# HDMI_OUT.net
KiCad netlist of a schematic drawn in Altium Designer
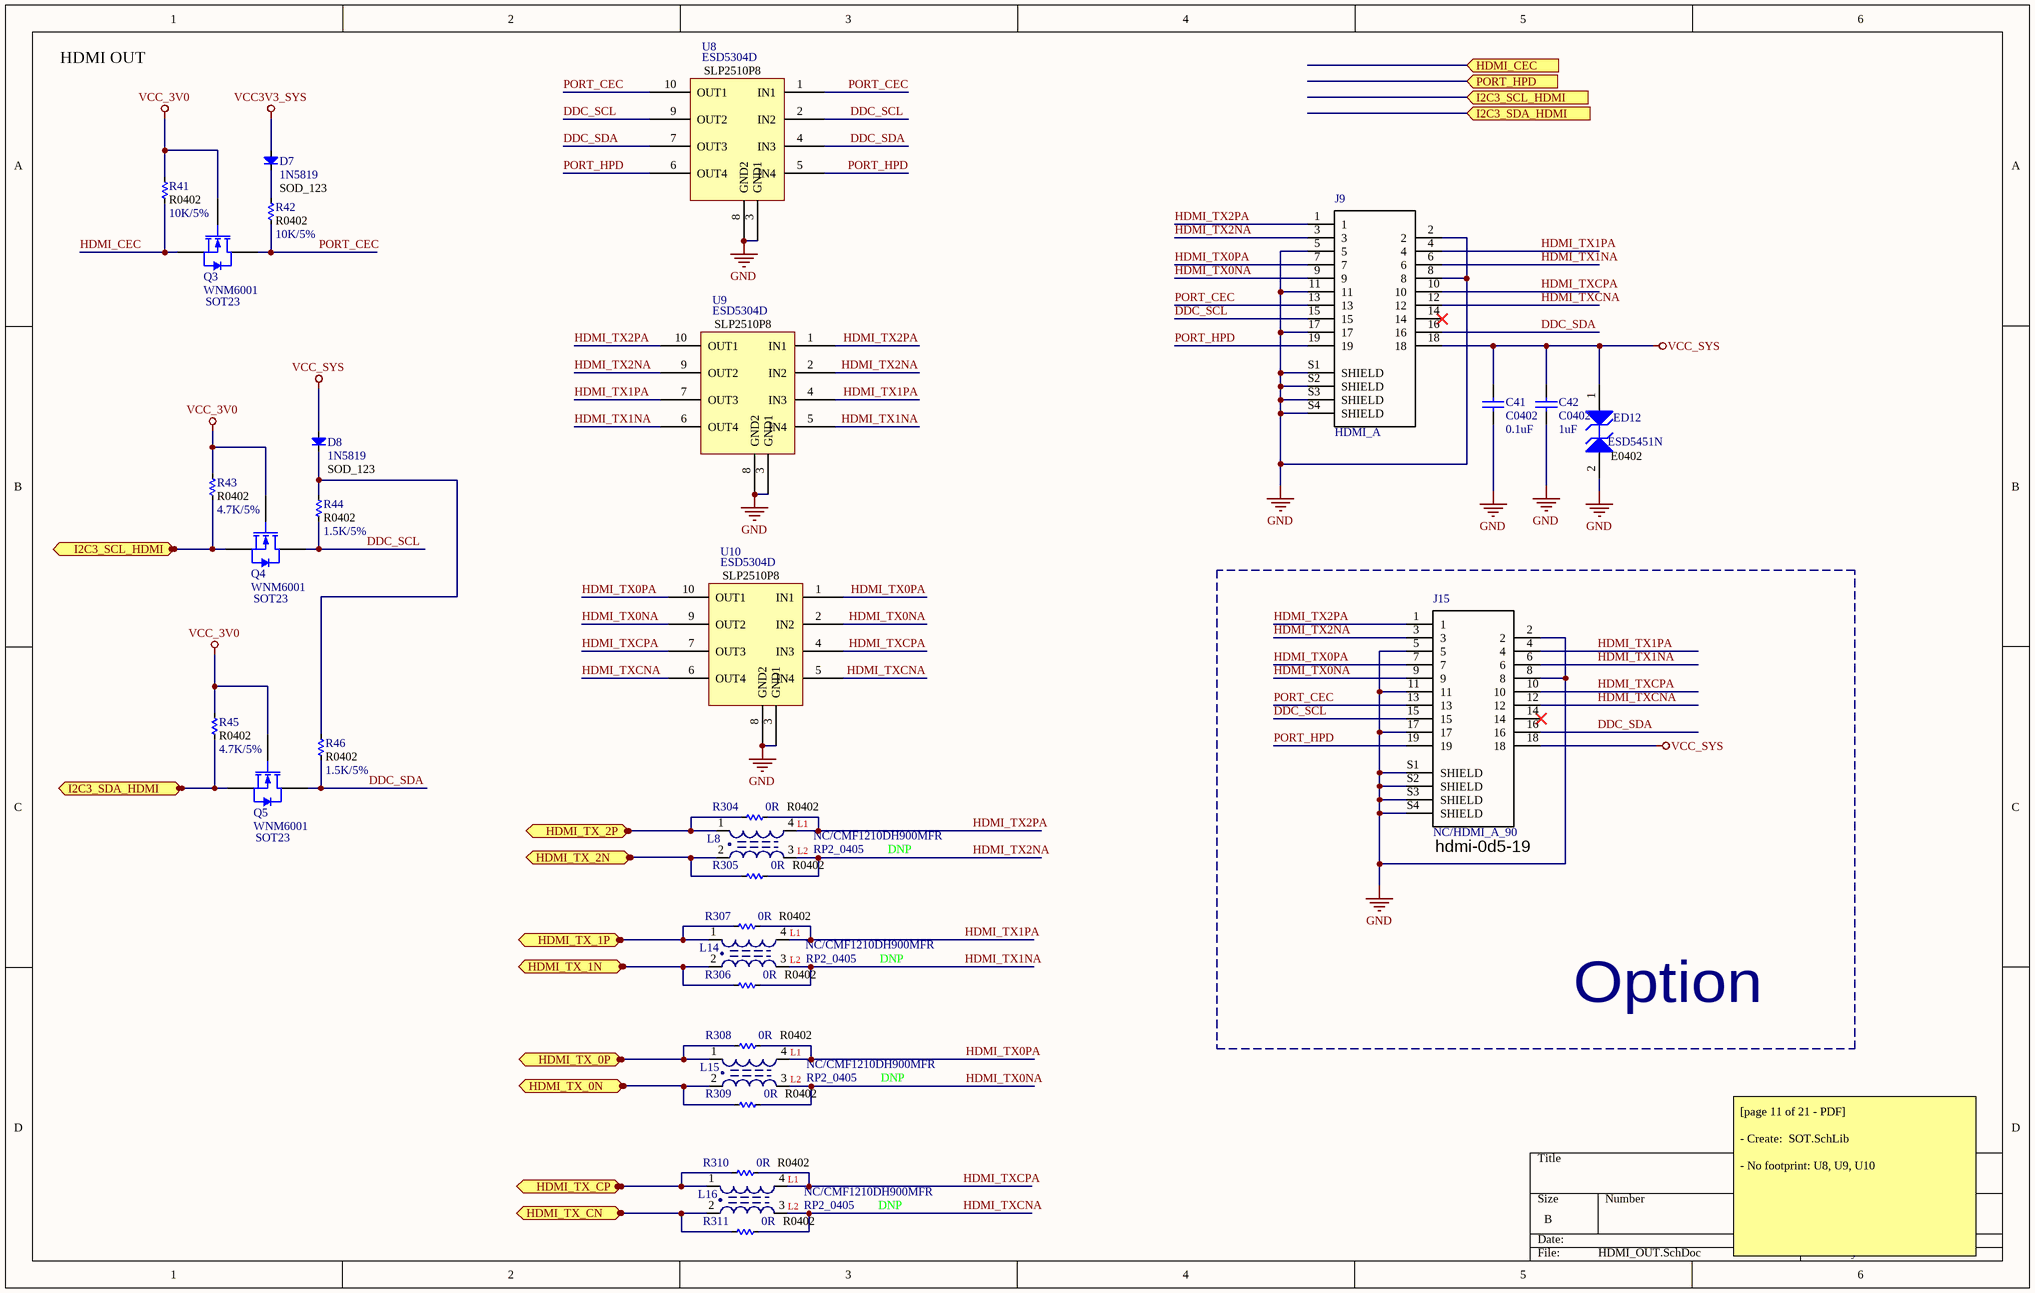
[diagram p0: HDMI_OUT.SchDoc]

(export (version "E")
  (design (tool "Eeschema 10.0.6"))
  (components
    (comp (ref "C41")
      (value "C0402")
      (footprint "C 0402")
      (description "Capacitor")
      (fields (field (name "ALTIUM_VALUE") "0.1uF") (field (name "PUBLISHER") "Altium Limited"))
      (libsource (lib "Miscellaneous Devices") (part "Cap"))
    )
    (comp (ref "C42")
      (value "C0402")
      (footprint "C 0402")
      (description "Capacitor")
      (fields (field (name "ALTIUM_VALUE") "1uF") (field (name "PUBLISHER") "Altium Limited"))
      (libsource (lib "Miscellaneous Devices") (part "Cap"))
    )
    (comp (ref "D7")
      (value "1N5819")
      (footprint "DIO-SMD-123")
      (description "Default Diode")
      (fields
        (field (name "TYPR") "SOD_123")
        (field (name "Comment") "Diode SMD")
        (field (name "PUBLISHER") "Altium Limited")
      )
      (libsource (lib "LIBRARY") (part "Diode SMD"))
    )
    (comp (ref "D8")
      (value "1N5819")
      (footprint "DIO-SMD-123")
      (description "Default Diode")
      (fields
        (field (name "TYPR") "SOD_123")
        (field (name "Comment") "Diode SMD")
        (field (name "PUBLISHER") "Altium Limited")
      )
      (libsource (lib "LIBRARY") (part "Diode SMD"))
    )
    (comp (ref "ED12")
      (value "ESD5451N")
      (footprint "DFN1006-2L")
      (description "600 W Peak Power Zener Transient Voltage Suppressor, Bidirectional, 2-Pin SMB, Tape and Reel")
      (fields
        (field (name "MANUFACTURER") "On Semiconductor")
        (field (name "PARTNUMBER") "1SMB54CAT3")
        (field (name "ALTIUM_UNNAMED_1") "E0402")
      )
      (libsource (lib "ON Semi Transient Voltage Suppressors (TVS)") (part "1SMB54CAT3"))
    )
    (comp (ref "J9")
      (value "HDMI_A")
      (footprint "*AMPHENOL_10029449-001RLF_10029449-001RLF(Primary)")
      (description "Connector, Hdmi Type a, Receptacle, 19 Position, Full Reel")
      (fields (field (name "MP") "10029449-001RLF") (field (name "MF") "Amphenol ICC"))
      (libsource (lib "10029449-001RLF") (part "10029449-001RLF"))
    )
    (comp (ref "J15")
      (value "NC/HDMI_A_90")
      (footprint "*AMPHENOL_10029449-001RLF_10029449-001RLF(Primary)")
      (description "Connector, Hdmi Type a, Receptacle, 19 Position, Full Reel")
      (fields
        (field (name "MP") "10029449-001RLF")
        (field (name "PACKAGE") "hdmi-0d5-19")
        (field (name "MF") "Amphenol ICC")
      )
      (libsource (lib "10029449-001RLF") (part "10029449-001RLF"))
    )
    (comp (ref "L8")
      (value "RP2_0405")
      (footprint "L-SMD-D-7.3x7.3")
      (fields
        (field (name "PARTNO") "7448709022")
        (field (name "MANUFACTURER") "Würth Elektronik eiSos GmbH")
        (field (name "ALTIUM_UNNAMED_1") "NC/CMF1210DH900MFR")
        (field (name "ALTIUM_UNNAMED_2") "DNP")
        (field (name "CREATED BY") "Christin Otto")
      )
      (libsource (lib "LIBRARY") (part "L-SMD-2"))
    )
    (comp (ref "L14")
      (value "RP2_0405")
      (footprint "L-SMD-D-7.3x7.3")
      (fields
        (field (name "PARTNO") "7448709022")
        (field (name "MANUFACTURER") "Würth Elektronik eiSos GmbH")
        (field (name "ALTIUM_UNNAMED_1") "NC/CMF1210DH900MFR")
        (field (name "ALTIUM_UNNAMED_2") "DNP")
        (field (name "CREATED BY") "Christin Otto")
      )
      (libsource (lib "LIBRARY") (part "L-SMD-2"))
    )
    (comp (ref "L15")
      (value "RP2_0405")
      (footprint "L-SMD-D-7.3x7.3")
      (fields
        (field (name "PARTNO") "7448709022")
        (field (name "MANUFACTURER") "Würth Elektronik eiSos GmbH")
        (field (name "ALTIUM_UNNAMED_1") "NC/CMF1210DH900MFR")
        (field (name "ALTIUM_UNNAMED_2") "DNP")
        (field (name "CREATED BY") "Christin Otto")
      )
      (libsource (lib "LIBRARY") (part "L-SMD-2"))
    )
    (comp (ref "L16")
      (value "RP2_0405")
      (footprint "L-SMD-D-7.3x7.3")
      (fields
        (field (name "PARTNO") "7448709022")
        (field (name "MANUFACTURER") "Würth Elektronik eiSos GmbH")
        (field (name "ALTIUM_UNNAMED_1") "NC/CMF1210DH900MFR")
        (field (name "ALTIUM_UNNAMED_2") "DNP")
        (field (name "CREATED BY") "Christin Otto")
      )
      (libsource (lib "LIBRARY") (part "L-SMD-2"))
    )
    (comp (ref "Q3")
      (value "WNM6001")
      (footprint "SOT23")
      (description "20V N-Channel Enhancement Mode MOSFET")
      (fields (field (name "PACKAGEREFERENCE") "SOT23") (field (name "PUBLISHER") "Altium Limited"))
      (libsource (lib "Zetex Discrete MOSFET") (part "ZXM61N02F"))
    )
    (comp (ref "Q4")
      (value "WNM6001")
      (footprint "SOT23")
      (description "20V N-Channel Enhancement Mode MOSFET")
      (fields (field (name "PACKAGEREFERENCE") "SOT23") (field (name "PUBLISHER") "Altium Limited"))
      (libsource (lib "Zetex Discrete MOSFET") (part "ZXM61N02F"))
    )
    (comp (ref "Q5")
      (value "WNM6001")
      (footprint "SOT23")
      (description "20V N-Channel Enhancement Mode MOSFET")
      (fields (field (name "PACKAGEREFERENCE") "SOT23") (field (name "PUBLISHER") "Altium Limited"))
      (libsource (lib "Zetex Discrete MOSFET") (part "ZXM61N02F"))
    )
    (comp (ref "R41")
      (value "R0402")
      (footprint "R 0402")
      (description "Resistor")
      (fields
        (field (name "MANUFACTURER") "Generic Components")
        (field (name "ALTIUM_VALUE") "10K/5%")
        (field (name "PUBLISHER") "Altium Hobart Technology Centre")
      )
      (libsource (lib "LIBRARY") (part "Res-SMD"))
    )
    (comp (ref "R42")
      (value "R0402")
      (footprint "R 0402")
      (description "Resistor")
      (fields
        (field (name "MANUFACTURER") "Generic Components")
        (field (name "ALTIUM_VALUE") "10K/5%")
        (field (name "PUBLISHER") "Altium Hobart Technology Centre")
      )
      (libsource (lib "LIBRARY") (part "Res-SMD"))
    )
    (comp (ref "R43")
      (value "R0402")
      (footprint "R 0402")
      (description "Resistor")
      (fields
        (field (name "MANUFACTURER") "Generic Components")
        (field (name "ALTIUM_VALUE") "4.7K/5%")
        (field (name "PUBLISHER") "Altium Hobart Technology Centre")
      )
      (libsource (lib "LIBRARY") (part "Res-SMD"))
    )
    (comp (ref "R44")
      (value "R0402")
      (footprint "R 0402")
      (description "Resistor")
      (fields
        (field (name "MANUFACTURER") "Generic Components")
        (field (name "ALTIUM_VALUE") "1.5K/5%")
        (field (name "PUBLISHER") "Altium Hobart Technology Centre")
      )
      (libsource (lib "LIBRARY") (part "Res-SMD"))
    )
    (comp (ref "R45")
      (value "R0402")
      (footprint "R 0402")
      (description "Resistor")
      (fields
        (field (name "MANUFACTURER") "Generic Components")
        (field (name "ALTIUM_VALUE") "4.7K/5%")
        (field (name "PUBLISHER") "Altium Hobart Technology Centre")
      )
      (libsource (lib "LIBRARY") (part "Res-SMD"))
    )
    (comp (ref "R46")
      (value "R0402")
      (footprint "R 0402")
      (description "Resistor")
      (fields
        (field (name "MANUFACTURER") "Generic Components")
        (field (name "ALTIUM_VALUE") "1.5K/5%")
        (field (name "PUBLISHER") "Altium Hobart Technology Centre")
      )
      (libsource (lib "LIBRARY") (part "Res-SMD"))
    )
    (comp (ref "R304")
      (value "R0402")
      (footprint "R 0402")
      (description "Resistor")
      (fields
        (field (name "MANUFACTURER") "Generic Components")
        (field (name "ALTIUM_VALUE") "0R")
        (field (name "PUBLISHER") "Altium Hobart Technology Centre")
      )
      (libsource (lib "LIBRARY") (part "Res-SMD"))
    )
    (comp (ref "R305")
      (value "R0402")
      (footprint "R 0402")
      (description "Resistor")
      (fields
        (field (name "MANUFACTURER") "Generic Components")
        (field (name "ALTIUM_VALUE") "0R")
        (field (name "PUBLISHER") "Altium Hobart Technology Centre")
      )
      (libsource (lib "LIBRARY") (part "Res-SMD"))
    )
    (comp (ref "R306")
      (value "R0402")
      (footprint "R 0402")
      (description "Resistor")
      (fields
        (field (name "MANUFACTURER") "Generic Components")
        (field (name "ALTIUM_VALUE") "0R")
        (field (name "PUBLISHER") "Altium Hobart Technology Centre")
      )
      (libsource (lib "LIBRARY") (part "Res-SMD"))
    )
    (comp (ref "R307")
      (value "R0402")
      (footprint "R 0402")
      (description "Resistor")
      (fields
        (field (name "MANUFACTURER") "Generic Components")
        (field (name "ALTIUM_VALUE") "0R")
        (field (name "PUBLISHER") "Altium Hobart Technology Centre")
      )
      (libsource (lib "LIBRARY") (part "Res-SMD"))
    )
    (comp (ref "R308")
      (value "R0402")
      (footprint "R 0402")
      (description "Resistor")
      (fields
        (field (name "MANUFACTURER") "Generic Components")
        (field (name "ALTIUM_VALUE") "0R")
        (field (name "PUBLISHER") "Altium Hobart Technology Centre")
      )
      (libsource (lib "LIBRARY") (part "Res-SMD"))
    )
    (comp (ref "R309")
      (value "R0402")
      (footprint "R 0402")
      (description "Resistor")
      (fields
        (field (name "MANUFACTURER") "Generic Components")
        (field (name "ALTIUM_VALUE") "0R")
        (field (name "PUBLISHER") "Altium Hobart Technology Centre")
      )
      (libsource (lib "LIBRARY") (part "Res-SMD"))
    )
    (comp (ref "R310")
      (value "R0402")
      (footprint "R 0402")
      (description "Resistor")
      (fields
        (field (name "MANUFACTURER") "Generic Components")
        (field (name "ALTIUM_VALUE") "0R")
        (field (name "PUBLISHER") "Altium Hobart Technology Centre")
      )
      (libsource (lib "LIBRARY") (part "Res-SMD"))
    )
    (comp (ref "R311")
      (value "R0402")
      (footprint "R 0402")
      (description "Resistor")
      (fields
        (field (name "MANUFACTURER") "Generic Components")
        (field (name "ALTIUM_VALUE") "0R")
        (field (name "PUBLISHER") "Altium Hobart Technology Centre")
      )
      (libsource (lib "LIBRARY") (part "Res-SMD"))
    )
    (comp (ref "U8")
      (value "ESD5304D")
      (footprint "RCLAMP0524PATCT")
      (libsource (lib "SOT") (part "SLP2510P8"))
    )
    (comp (ref "U9")
      (value "ESD5304D")
      (footprint "RCLAMP0524PATCT")
      (libsource (lib "SOT") (part "SLP2510P8"))
    )
    (comp (ref "U10")
      (value "ESD5304D")
      (footprint "RCLAMP0524PATCT")
      (libsource (lib "SOT") (part "SLP2510P8"))
    )
  )
  (nets
    (net (code "1") (name "/DDC_SCL") (class "Default")
      (node (ref "J15") (pin "15") (pinfunction "15_15") (pintype "passive"))
      (node (ref "J9") (pin "15") (pinfunction "15_15") (pintype "passive"))
      (node (ref "Q4") (pin "1") (pinfunction "D_1") (pintype "passive"))
      (node (ref "R44") (pin "1") (pinfunction "1_1") (pintype "passive"))
      (node (ref "U8") (pin "2") (pinfunction "IN2_2") (pintype "passive"))
      (node (ref "U8") (pin "9") (pinfunction "OUT2_9") (pintype "passive"))
    )
    (net (code "2") (name "/DDC_SDA") (class "Default")
      (node (ref "J15") (pin "16") (pinfunction "16_16") (pintype "passive"))
      (node (ref "J9") (pin "16") (pinfunction "16_16") (pintype "passive"))
      (node (ref "Q5") (pin "1") (pinfunction "D_1") (pintype "passive"))
      (node (ref "R46") (pin "1") (pinfunction "1_1") (pintype "passive"))
      (node (ref "U8") (pin "4") (pinfunction "IN3_4") (pintype "passive"))
      (node (ref "U8") (pin "7") (pinfunction "OUT3_7") (pintype "passive"))
    )
    (net (code "3") (name "/HDMI_CEC") (class "Default")
      (node (ref "Q3") (pin "2") (pinfunction "S_2") (pintype "passive"))
      (node (ref "R41") (pin "1") (pinfunction "1_1") (pintype "passive"))
    )
    (net (code "4") (name "/HDMI_TX0NA") (class "Default")
      (node (ref "J15") (pin "9") (pinfunction "9_9") (pintype "passive"))
      (node (ref "J9") (pin "9") (pinfunction "9_9") (pintype "passive"))
      (node (ref "L15") (pin "3") (pinfunction "3_3") (pintype "passive"))
      (node (ref "R309") (pin "1") (pinfunction "1_1") (pintype "passive"))
      (node (ref "U10") (pin "2") (pinfunction "IN2_2") (pintype "passive"))
      (node (ref "U10") (pin "9") (pinfunction "OUT2_9") (pintype "passive"))
    )
    (net (code "5") (name "/HDMI_TX0PA") (class "Default")
      (node (ref "J15") (pin "7") (pinfunction "7_7") (pintype "passive"))
      (node (ref "J9") (pin "7") (pinfunction "7_7") (pintype "passive"))
      (node (ref "L15") (pin "4") (pinfunction "4_4") (pintype "passive"))
      (node (ref "R308") (pin "1") (pinfunction "1_1") (pintype "passive"))
      (node (ref "U10") (pin "1") (pinfunction "IN1_1") (pintype "passive"))
      (node (ref "U10") (pin "10") (pinfunction "OUT1_10") (pintype "passive"))
    )
    (net (code "6") (name "/HDMI_TX1NA") (class "Default")
      (node (ref "J15") (pin "6") (pinfunction "6_6") (pintype "passive"))
      (node (ref "J9") (pin "6") (pinfunction "6_6") (pintype "passive"))
      (node (ref "L14") (pin "3") (pinfunction "3_3") (pintype "passive"))
      (node (ref "R306") (pin "1") (pinfunction "1_1") (pintype "passive"))
      (node (ref "U9") (pin "5") (pinfunction "IN4_5") (pintype "passive"))
      (node (ref "U9") (pin "6") (pinfunction "OUT4_6") (pintype "passive"))
    )
    (net (code "7") (name "/HDMI_TX1PA") (class "Default")
      (node (ref "J15") (pin "4") (pinfunction "4_4") (pintype "passive"))
      (node (ref "J9") (pin "4") (pinfunction "4_4") (pintype "passive"))
      (node (ref "L14") (pin "4") (pinfunction "4_4") (pintype "passive"))
      (node (ref "R307") (pin "1") (pinfunction "1_1") (pintype "passive"))
      (node (ref "U9") (pin "4") (pinfunction "IN3_4") (pintype "passive"))
      (node (ref "U9") (pin "7") (pinfunction "OUT3_7") (pintype "passive"))
    )
    (net (code "8") (name "/HDMI_TX2NA") (class "Default")
      (node (ref "J15") (pin "3") (pinfunction "3_3") (pintype "passive"))
      (node (ref "J9") (pin "3") (pinfunction "3_3") (pintype "passive"))
      (node (ref "L8") (pin "3") (pinfunction "3_3") (pintype "passive"))
      (node (ref "R305") (pin "1") (pinfunction "1_1") (pintype "passive"))
      (node (ref "U9") (pin "2") (pinfunction "IN2_2") (pintype "passive"))
      (node (ref "U9") (pin "9") (pinfunction "OUT2_9") (pintype "passive"))
    )
    (net (code "9") (name "/HDMI_TX2PA") (class "Default")
      (node (ref "J15") (pin "1") (pinfunction "1_1") (pintype "passive"))
      (node (ref "J9") (pin "1") (pinfunction "1_1") (pintype "passive"))
      (node (ref "L8") (pin "4") (pinfunction "4_4") (pintype "passive"))
      (node (ref "R304") (pin "1") (pinfunction "1_1") (pintype "passive"))
      (node (ref "U9") (pin "1") (pinfunction "IN1_1") (pintype "passive"))
      (node (ref "U9") (pin "10") (pinfunction "OUT1_10") (pintype "passive"))
    )
    (net (code "10") (name "/HDMI_TXCNA") (class "Default")
      (node (ref "J15") (pin "12") (pinfunction "12_12") (pintype "passive"))
      (node (ref "J9") (pin "12") (pinfunction "12_12") (pintype "passive"))
      (node (ref "L16") (pin "3") (pinfunction "3_3") (pintype "passive"))
      (node (ref "R311") (pin "1") (pinfunction "1_1") (pintype "passive"))
      (node (ref "U10") (pin "5") (pinfunction "IN4_5") (pintype "passive"))
      (node (ref "U10") (pin "6") (pinfunction "OUT4_6") (pintype "passive"))
    )
    (net (code "11") (name "/HDMI_TXCPA") (class "Default")
      (node (ref "J15") (pin "10") (pinfunction "10_10") (pintype "passive"))
      (node (ref "J9") (pin "10") (pinfunction "10_10") (pintype "passive"))
      (node (ref "L16") (pin "4") (pinfunction "4_4") (pintype "passive"))
      (node (ref "R310") (pin "1") (pinfunction "1_1") (pintype "passive"))
      (node (ref "U10") (pin "4") (pinfunction "IN3_4") (pintype "passive"))
      (node (ref "U10") (pin "7") (pinfunction "OUT3_7") (pintype "passive"))
    )
    (net (code "12") (name "/HDMI_TX_0N") (class "Default")
      (node (ref "L15") (pin "2") (pinfunction "2_2") (pintype "passive"))
      (node (ref "R309") (pin "2") (pinfunction "2_2") (pintype "passive"))
    )
    (net (code "13") (name "/HDMI_TX_0P") (class "Default")
      (node (ref "L15") (pin "1") (pinfunction "1_1") (pintype "passive"))
      (node (ref "R308") (pin "2") (pinfunction "2_2") (pintype "passive"))
    )
    (net (code "14") (name "/HDMI_TX_1N") (class "Default")
      (node (ref "L14") (pin "2") (pinfunction "2_2") (pintype "passive"))
      (node (ref "R306") (pin "2") (pinfunction "2_2") (pintype "passive"))
    )
    (net (code "15") (name "/HDMI_TX_1P") (class "Default")
      (node (ref "L14") (pin "1") (pinfunction "1_1") (pintype "passive"))
      (node (ref "R307") (pin "2") (pinfunction "2_2") (pintype "passive"))
    )
    (net (code "16") (name "/HDMI_TX_2N") (class "Default")
      (node (ref "L8") (pin "2") (pinfunction "2_2") (pintype "passive"))
      (node (ref "R305") (pin "2") (pinfunction "2_2") (pintype "passive"))
    )
    (net (code "17") (name "/HDMI_TX_2P") (class "Default")
      (node (ref "L8") (pin "1") (pinfunction "1_1") (pintype "passive"))
      (node (ref "R304") (pin "2") (pinfunction "2_2") (pintype "passive"))
    )
    (net (code "18") (name "/HDMI_TX_CN") (class "Default")
      (node (ref "L16") (pin "2") (pinfunction "2_2") (pintype "passive"))
      (node (ref "R311") (pin "2") (pinfunction "2_2") (pintype "passive"))
    )
    (net (code "19") (name "/HDMI_TX_CP") (class "Default")
      (node (ref "L16") (pin "1") (pinfunction "1_1") (pintype "passive"))
      (node (ref "R310") (pin "2") (pinfunction "2_2") (pintype "passive"))
    )
    (net (code "20") (name "/I2C3_SCL_HDMI") (class "Default")
      (node (ref "Q4") (pin "2") (pinfunction "S_2") (pintype "passive"))
      (node (ref "R43") (pin "1") (pinfunction "1_1") (pintype "passive"))
    )
    (net (code "21") (name "/I2C3_SDA_HDMI") (class "Default")
      (node (ref "Q5") (pin "2") (pinfunction "S_2") (pintype "passive"))
      (node (ref "R45") (pin "1") (pinfunction "1_1") (pintype "passive"))
    )
    (net (code "22") (name "/PORT_CEC") (class "Default")
      (node (ref "J15") (pin "13") (pinfunction "13_13") (pintype "passive"))
      (node (ref "J9") (pin "13") (pinfunction "13_13") (pintype "passive"))
      (node (ref "Q3") (pin "1") (pinfunction "D_1") (pintype "passive"))
      (node (ref "R42") (pin "1") (pinfunction "1_1") (pintype "passive"))
      (node (ref "U8") (pin "1") (pinfunction "IN1_1") (pintype "passive"))
      (node (ref "U8") (pin "10") (pinfunction "OUT1_10") (pintype "passive"))
    )
    (net (code "23") (name "/PORT_HPD") (class "Default")
      (node (ref "J15") (pin "19") (pinfunction "19_19") (pintype "passive"))
      (node (ref "J9") (pin "19") (pinfunction "19_19") (pintype "passive"))
      (node (ref "U8") (pin "5") (pinfunction "IN4_5") (pintype "passive"))
      (node (ref "U8") (pin "6") (pinfunction "OUT4_6") (pintype "passive"))
    )
    (net (code "24") (name "GND") (class "Default")
      (node (ref "C41") (pin "2") (pinfunction "2_2") (pintype "passive"))
      (node (ref "C42") (pin "2") (pinfunction "2_2") (pintype "passive"))
      (node (ref "ED12") (pin "2") (pinfunction "A2_2") (pintype "passive"))
      (node (ref "J15") (pin "11") (pinfunction "11_11") (pintype "passive"))
      (node (ref "J15") (pin "17") (pinfunction "17_17") (pintype "passive"))
      (node (ref "J15") (pin "2") (pinfunction "2_2") (pintype "passive"))
      (node (ref "J15") (pin "5") (pinfunction "5_5") (pintype "passive"))
      (node (ref "J15") (pin "8") (pinfunction "8_8") (pintype "passive"))
      (node (ref "J15") (pin "S1") (pinfunction "SHIELD_S1") (pintype "passive"))
      (node (ref "J15") (pin "S2") (pinfunction "SHIELD_S2") (pintype "passive"))
      (node (ref "J15") (pin "S3") (pinfunction "SHIELD_S3") (pintype "passive"))
      (node (ref "J15") (pin "S4") (pinfunction "SHIELD_S4") (pintype "passive"))
      (node (ref "J9") (pin "11") (pinfunction "11_11") (pintype "passive"))
      (node (ref "J9") (pin "17") (pinfunction "17_17") (pintype "passive"))
      (node (ref "J9") (pin "2") (pinfunction "2_2") (pintype "passive"))
      (node (ref "J9") (pin "5") (pinfunction "5_5") (pintype "passive"))
      (node (ref "J9") (pin "8") (pinfunction "8_8") (pintype "passive"))
      (node (ref "J9") (pin "S1") (pinfunction "SHIELD_S1") (pintype "passive"))
      (node (ref "J9") (pin "S2") (pinfunction "SHIELD_S2") (pintype "passive"))
      (node (ref "J9") (pin "S3") (pinfunction "SHIELD_S3") (pintype "passive"))
      (node (ref "J9") (pin "S4") (pinfunction "SHIELD_S4") (pintype "passive"))
      (node (ref "U10") (pin "3") (pinfunction "GND1_3") (pintype "passive"))
      (node (ref "U10") (pin "8") (pinfunction "GND2_8") (pintype "passive"))
      (node (ref "U8") (pin "3") (pinfunction "GND1_3") (pintype "passive"))
      (node (ref "U8") (pin "8") (pinfunction "GND2_8") (pintype "passive"))
      (node (ref "U9") (pin "3") (pinfunction "GND1_3") (pintype "passive"))
      (node (ref "U9") (pin "8") (pinfunction "GND2_8") (pintype "passive"))
    )
    (net (code "25") (name "Net-(D7-K)") (class "Default")
      (node (ref "D7") (pin "2") (pinfunction "K_2") (pintype "passive"))
      (node (ref "R42") (pin "2") (pinfunction "2_2") (pintype "passive"))
    )
    (net (code "26") (name "Net-(D8-K)") (class "Default")
      (node (ref "D8") (pin "2") (pinfunction "K_2") (pintype "passive"))
      (node (ref "R44") (pin "2") (pinfunction "2_2") (pintype "passive"))
      (node (ref "R46") (pin "2") (pinfunction "2_2") (pintype "passive"))
    )
    (net (code "27") (name "VCC3V3_SYS") (class "Default")
      (node (ref "D7") (pin "1") (pinfunction "A_1") (pintype "passive"))
    )
    (net (code "28") (name "VCC_3V0") (class "Default")
      (node (ref "Q3") (pin "3") (pinfunction "G_3") (pintype "passive"))
      (node (ref "Q4") (pin "3") (pinfunction "G_3") (pintype "passive"))
      (node (ref "Q5") (pin "3") (pinfunction "G_3") (pintype "passive"))
      (node (ref "R41") (pin "2") (pinfunction "2_2") (pintype "passive"))
      (node (ref "R43") (pin "2") (pinfunction "2_2") (pintype "passive"))
      (node (ref "R45") (pin "2") (pinfunction "2_2") (pintype "passive"))
    )
    (net (code "29") (name "VCC_SYS") (class "Default")
      (node (ref "C41") (pin "1") (pinfunction "1_1") (pintype "passive"))
      (node (ref "C42") (pin "1") (pinfunction "1_1") (pintype "passive"))
      (node (ref "D8") (pin "1") (pinfunction "A_1") (pintype "passive"))
      (node (ref "ED12") (pin "1") (pinfunction "A1_1") (pintype "passive"))
      (node (ref "J15") (pin "18") (pinfunction "18_18") (pintype "passive"))
      (node (ref "J9") (pin "18") (pinfunction "18_18") (pintype "passive"))
    )
    (net (code "30") (name "unconnected-(J9-Pad14)") (class "Default")
      (node (ref "J9") (pin "14") (pinfunction "14_14") (pintype "passive+no_connect"))
    )
    (net (code "31") (name "unconnected-(J15-Pad14)") (class "Default")
      (node (ref "J15") (pin "14") (pinfunction "14_14") (pintype "passive+no_connect"))
    )
  )
)
